# tactile_power.net
KiCad netlist of a schematic drawn in Altium Designer
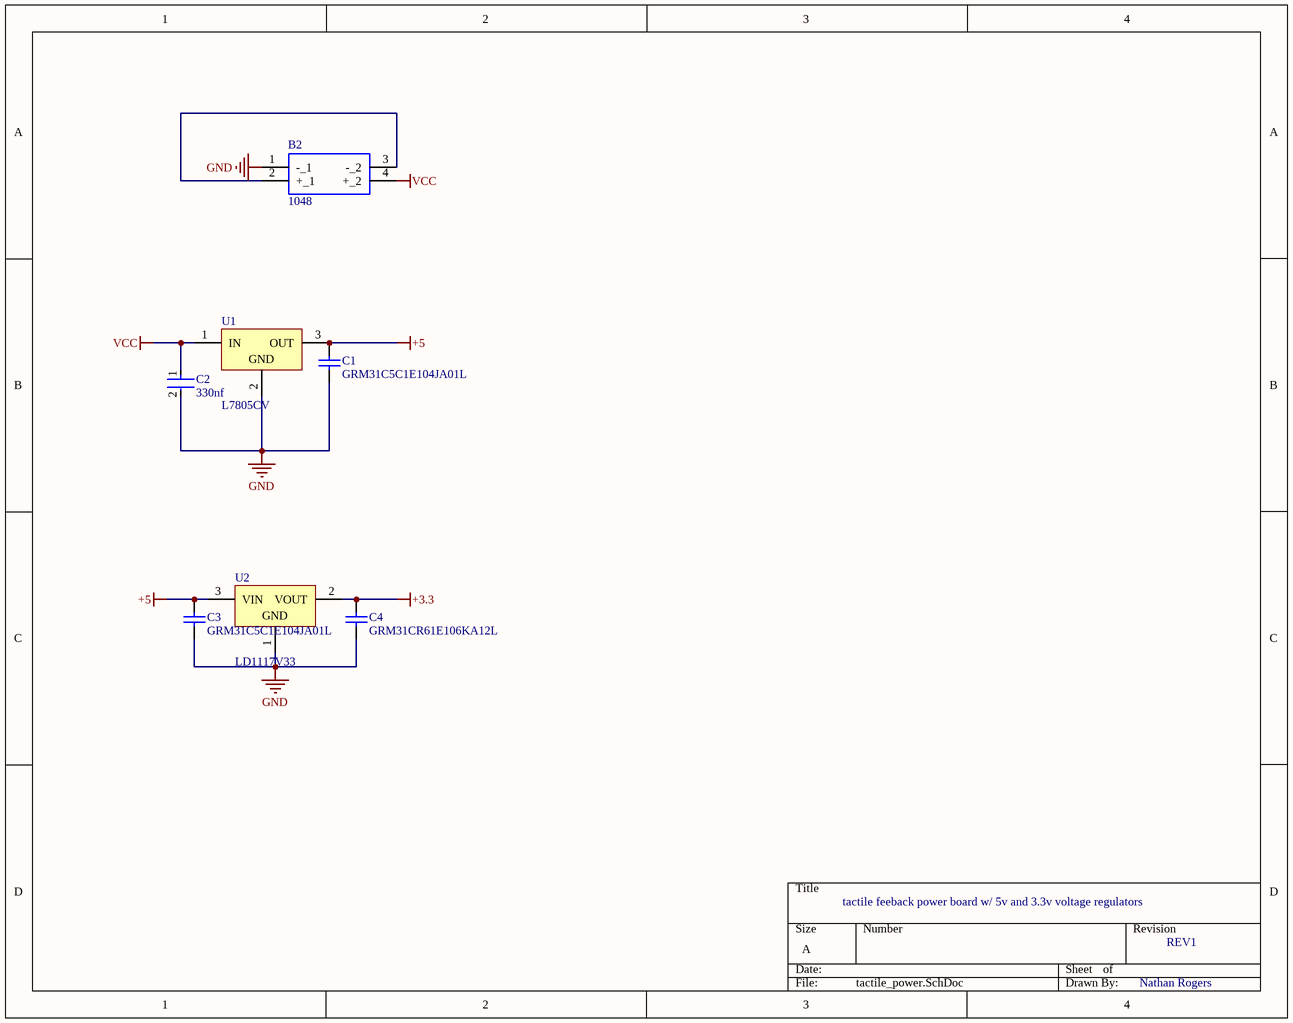
[diagram p0: tactile_power.SchDoc]

(export (version "E")
  (design (tool "Eeschema 10.0.6"))
  (components
    (comp (ref "B2")
      (value "1048")
      (footprint "1048")
      (description "KEYSTONE - 1048 - BATTERY HOLDER, 18650 LI-ION, 2CELL, SMD")
      (fields (field (name "MOUSER PART NUMBER") "534-1048"))
      (libsource (lib "Worcester Polytechnical Institute") (part "1048"))
    )
    (comp (ref "C1")
      (value "GRM31C5C1E104JA01L")
      (footprint "CAPC3216X180X55LL20T25")
      (description "Chip Capacitor, 100 nF, +/- 5%, 25 V, -55 to 125 degC, 1206 (3216 Metric), RoHS, Tape and Reel")
      (fields (field (name "MANUFACTURER") "Murata"))
      (libsource (lib "Altium Content Vault") (part "CAP-NP-2"))
    )
    (comp (ref "C2")
      (value "330nf")
      (footprint "FP-1206-L_3_2_0_2-W_1_6_0-IPC_B")
      (description "General Purpose Ceramic Capacitor, 1206, 330nF, 10%, X7R, 15%, 50V")
      (fields (field (name "TOLERANCE") "10%") (field (name "VOLTAGE") "25V"))
      (libsource (lib "Altium Content Vault") (part "b4654b650e69147ec39a6b967a45e02"))
    )
    (comp (ref "C3")
      (value "GRM31C5C1E104JA01L")
      (footprint "CAPC3216X180X55LL20T25")
      (description "Chip Capacitor, 100 nF, +/- 5%, 25 V, -55 to 125 degC, 1206 (3216 Metric), RoHS, Tape and Reel")
      (fields (field (name "MANUFACTURER") "Murata"))
      (libsource (lib "Altium Content Vault") (part "CAP-NP-2"))
    )
    (comp (ref "C4")
      (value "GRM31CR61E106KA12L")
      (footprint "CAPC3216X180X55ML20T25")
      (description "Chip Capacitor, 10 uF, +/- 10%, 25 V, -55 to 85 degC, 1206 (3216 Metric), RoHS, Tape and Reel")
      (fields (field (name "MANUFACTURER") "Murata") (field (name "TOLERANCE") "10%"))
      (libsource (lib "Altium Content Vault") (part "CAP-NP-2"))
    )
    (comp (ref "U1")
      (value "L7805CV")
      (footprint "TO220")
      (description "Positive Voltage Regulator, 5V, 3-Pin TO-220")
      (libsource (lib "Altium Content Vault") (part "PM-REG-L4940-SIL3"))
    )
    (comp (ref "U2")
      (value "LD1117V33")
      (footprint "TO220")
      (description "Fixed Low Drop Positive Voltage Regulator, 3.3V, 3-Pin TO-220")
      (libsource (lib "Altium Content Vault") (part "PM-REG-LD1117V-SIL3"))
    )
  )
  (nets
    (net (code "1") (name "+3.3") (class "Default")
      (node (ref "C4") (pin "2") (pinfunction "2_2") (pintype "passive"))
      (node (ref "U2") (pin "2") (pinfunction "VOUT_2") (pintype "power_in"))
    )
    (net (code "2") (name "+5") (class "Default")
      (node (ref "C1") (pin "2") (pinfunction "2_2") (pintype "passive"))
      (node (ref "C3") (pin "2") (pinfunction "2_2") (pintype "passive"))
      (node (ref "U1") (pin "3") (pinfunction "OUT_3") (pintype "power_in"))
      (node (ref "U2") (pin "3") (pinfunction "VIN_3") (pintype "power_in"))
    )
    (net (code "3") (name "GND") (class "Default")
      (node (ref "B2") (pin "1") (pinfunction "-_1_1") (pintype "passive"))
      (node (ref "C1") (pin "1") (pinfunction "1_1") (pintype "passive"))
      (node (ref "C2") (pin "2") (pinfunction "2_2") (pintype "passive"))
      (node (ref "C3") (pin "1") (pinfunction "1_1") (pintype "passive"))
      (node (ref "C4") (pin "1") (pinfunction "1_1") (pintype "passive"))
      (node (ref "U1") (pin "2") (pinfunction "GND_2") (pintype "power_in"))
      (node (ref "U2") (pin "1") (pinfunction "GND_1") (pintype "power_in"))
    )
    (net (code "4") (name "Net-(B2-+_1)") (class "Default")
      (node (ref "B2") (pin "2") (pinfunction "+_1_2") (pintype "passive"))
      (node (ref "B2") (pin "3") (pinfunction "-_2_3") (pintype "passive"))
    )
    (net (code "5") (name "VCC") (class "Default")
      (node (ref "B2") (pin "4") (pinfunction "+_2_4") (pintype "passive"))
      (node (ref "C2") (pin "1") (pinfunction "1_1") (pintype "passive"))
      (node (ref "U1") (pin "1") (pinfunction "IN_1") (pintype "power_in"))
    )
  )
)
